# BMS_master_board.net
KiCad netlist of a schematic drawn in EAGLE
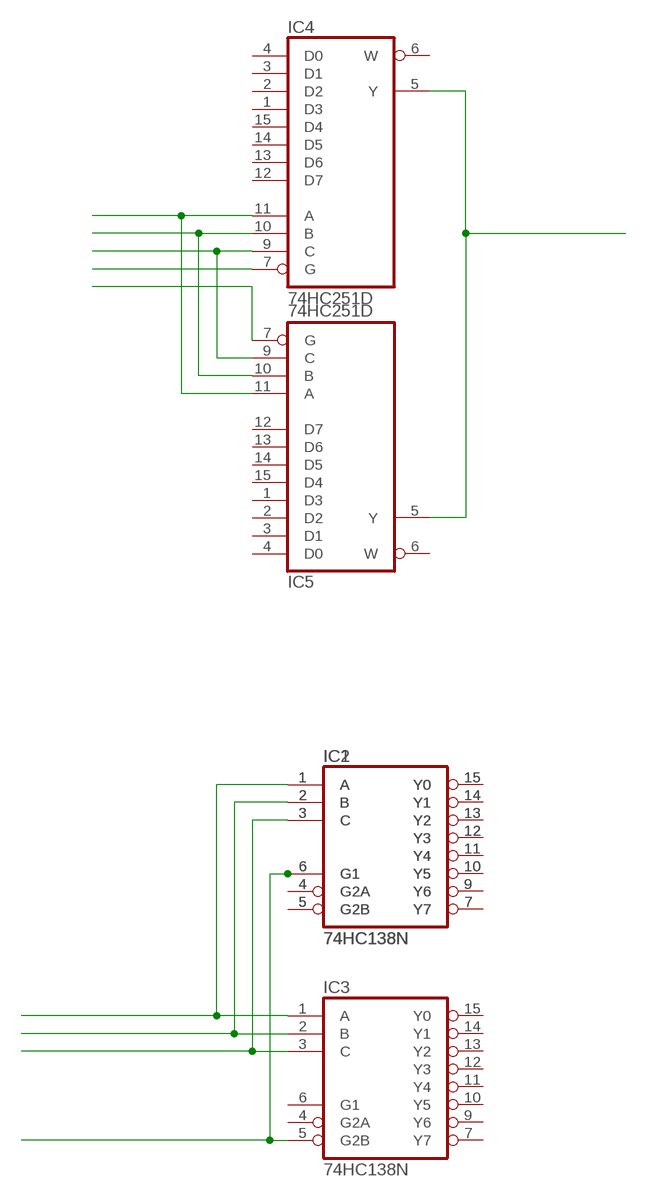
[diagram p0: schematic, sheet 1]

(export (version "E")
  (design (tool "Eeschema 10.0.6"))
  (components
    (comp (ref "IC1")
      (value "74HC138N")
      (footprint "eagle-import:DIL16")
      (libsource (lib "eagle-import") (part "74138NHC"))
    )
    (comp (ref "IC2")
      (value "74HC138N")
      (footprint "eagle-import:DIL16")
      (libsource (lib "eagle-import") (part "74138NHC"))
    )
    (comp (ref "IC3")
      (value "74HC138N")
      (footprint "eagle-import:DIL16")
      (libsource (lib "eagle-import") (part "74138NHC"))
    )
    (comp (ref "IC4")
      (value "74HC251D")
      (footprint "eagle-import:SO16")
      (libsource (lib "eagle-import") (part "74251DHC"))
    )
    (comp (ref "IC5")
      (value "74HC251D")
      (footprint "eagle-import:SO16")
      (libsource (lib "eagle-import") (part "74251DHC"))
    )
  )
  (nets
    (net (code "1") (name "Net-(IC1A-A)") (class "Default")
      (node (ref "IC1") (pin "1") (pinfunction "A_1") (pintype "input"))
      (node (ref "IC2") (pin "1") (pinfunction "A_1") (pintype "input"))
      (node (ref "IC3") (pin "1") (pinfunction "A_1") (pintype "input"))
    )
    (net (code "2") (name "Net-(IC1A-B)") (class "Default")
      (node (ref "IC1") (pin "2") (pinfunction "B_2") (pintype "input"))
      (node (ref "IC2") (pin "2") (pinfunction "B_2") (pintype "input"))
      (node (ref "IC3") (pin "2") (pinfunction "B_2") (pintype "input"))
    )
    (net (code "3") (name "Net-(IC1A-C)") (class "Default")
      (node (ref "IC1") (pin "3") (pinfunction "C_3") (pintype "input"))
      (node (ref "IC2") (pin "3") (pinfunction "C_3") (pintype "input"))
      (node (ref "IC3") (pin "3") (pinfunction "C_3") (pintype "input"))
    )
    (net (code "4") (name "Net-(IC1A-G1)") (class "Default")
      (node (ref "IC1") (pin "6") (pinfunction "G1_6") (pintype "input"))
      (node (ref "IC2") (pin "6") (pinfunction "G1_6") (pintype "input"))
      (node (ref "IC3") (pin "5") (pinfunction "G2B_5") (pintype "input"))
    )
    (net (code "5") (name "Net-(IC1A-G2A)") (class "Default")
      (node (ref "IC1") (pin "4") (pinfunction "G2A_4") (pintype "input"))
      (node (ref "IC2") (pin "4") (pinfunction "G2A_4") (pintype "input"))
    )
    (net (code "6") (name "Net-(IC1A-G2B)") (class "Default")
      (node (ref "IC1") (pin "5") (pinfunction "G2B_5") (pintype "input"))
      (node (ref "IC2") (pin "5") (pinfunction "G2B_5") (pintype "input"))
    )
    (net (code "7") (name "Net-(IC1A-Y0)") (class "Default")
      (node (ref "IC1") (pin "15") (pinfunction "Y0_15") (pintype "output"))
      (node (ref "IC2") (pin "15") (pinfunction "Y0_15") (pintype "output"))
    )
    (net (code "8") (name "Net-(IC1A-Y1)") (class "Default")
      (node (ref "IC1") (pin "14") (pinfunction "Y1_14") (pintype "output"))
      (node (ref "IC2") (pin "14") (pinfunction "Y1_14") (pintype "output"))
    )
    (net (code "9") (name "Net-(IC1A-Y2)") (class "Default")
      (node (ref "IC1") (pin "13") (pinfunction "Y2_13") (pintype "output"))
      (node (ref "IC2") (pin "13") (pinfunction "Y2_13") (pintype "output"))
    )
    (net (code "10") (name "Net-(IC1A-Y3)") (class "Default")
      (node (ref "IC1") (pin "12") (pinfunction "Y3_12") (pintype "output"))
      (node (ref "IC2") (pin "12") (pinfunction "Y3_12") (pintype "output"))
    )
    (net (code "11") (name "Net-(IC1A-Y4)") (class "Default")
      (node (ref "IC1") (pin "11") (pinfunction "Y4_11") (pintype "output"))
      (node (ref "IC2") (pin "11") (pinfunction "Y4_11") (pintype "output"))
    )
    (net (code "12") (name "Net-(IC1A-Y5)") (class "Default")
      (node (ref "IC1") (pin "10") (pinfunction "Y5_10") (pintype "output"))
      (node (ref "IC2") (pin "10") (pinfunction "Y5_10") (pintype "output"))
    )
    (net (code "13") (name "Net-(IC1A-Y6)") (class "Default")
      (node (ref "IC1") (pin "9") (pinfunction "Y6_9") (pintype "output"))
      (node (ref "IC2") (pin "9") (pinfunction "Y6_9") (pintype "output"))
    )
    (net (code "14") (name "Net-(IC1A-Y7)") (class "Default")
      (node (ref "IC1") (pin "7") (pinfunction "Y7_7") (pintype "output"))
      (node (ref "IC2") (pin "7") (pinfunction "Y7_7") (pintype "output"))
    )
    (net (code "15") (name "Net-(IC4A-A)") (class "Default")
      (node (ref "IC4") (pin "11") (pinfunction "A_11") (pintype "input"))
      (node (ref "IC5") (pin "11") (pinfunction "A_11") (pintype "input"))
    )
    (net (code "16") (name "Net-(IC4A-B)") (class "Default")
      (node (ref "IC4") (pin "10") (pinfunction "B_10") (pintype "input"))
      (node (ref "IC5") (pin "10") (pinfunction "B_10") (pintype "input"))
    )
    (net (code "17") (name "Net-(IC4A-C)") (class "Default")
      (node (ref "IC4") (pin "9") (pinfunction "C_9") (pintype "input"))
      (node (ref "IC5") (pin "9") (pinfunction "C_9") (pintype "input"))
    )
    (net (code "18") (name "Net-(IC4A-Y)") (class "Default")
      (node (ref "IC4") (pin "5") (pinfunction "Y_5") (pintype "tri_state"))
      (node (ref "IC5") (pin "5") (pinfunction "Y_5") (pintype "tri_state"))
    )
    (net (code "19") (name "unconnected-(IC3A-G1-Pad6)") (class "Default")
      (node (ref "IC3") (pin "6") (pinfunction "G1_6") (pintype "input"))
    )
    (net (code "20") (name "unconnected-(IC3A-G2A-Pad4)") (class "Default")
      (node (ref "IC3") (pin "4") (pinfunction "G2A_4") (pintype "input"))
    )
    (net (code "21") (name "unconnected-(IC3A-Y0-Pad15)") (class "Default")
      (node (ref "IC3") (pin "15") (pinfunction "Y0_15") (pintype "output"))
    )
    (net (code "22") (name "unconnected-(IC3A-Y1-Pad14)") (class "Default")
      (node (ref "IC3") (pin "14") (pinfunction "Y1_14") (pintype "output"))
    )
    (net (code "23") (name "unconnected-(IC3A-Y2-Pad13)") (class "Default")
      (node (ref "IC3") (pin "13") (pinfunction "Y2_13") (pintype "output"))
    )
    (net (code "24") (name "unconnected-(IC3A-Y3-Pad12)") (class "Default")
      (node (ref "IC3") (pin "12") (pinfunction "Y3_12") (pintype "output"))
    )
    (net (code "25") (name "unconnected-(IC3A-Y4-Pad11)") (class "Default")
      (node (ref "IC3") (pin "11") (pinfunction "Y4_11") (pintype "output"))
    )
    (net (code "26") (name "unconnected-(IC3A-Y5-Pad10)") (class "Default")
      (node (ref "IC3") (pin "10") (pinfunction "Y5_10") (pintype "output"))
    )
    (net (code "27") (name "unconnected-(IC3A-Y6-Pad9)") (class "Default")
      (node (ref "IC3") (pin "9") (pinfunction "Y6_9") (pintype "output"))
    )
    (net (code "28") (name "unconnected-(IC3A-Y7-Pad7)") (class "Default")
      (node (ref "IC3") (pin "7") (pinfunction "Y7_7") (pintype "output"))
    )
    (net (code "29") (name "unconnected-(IC4A-D0-Pad4)") (class "Default")
      (node (ref "IC4") (pin "4") (pinfunction "D0_4") (pintype "input"))
    )
    (net (code "30") (name "unconnected-(IC4A-D1-Pad3)") (class "Default")
      (node (ref "IC4") (pin "3") (pinfunction "D1_3") (pintype "input"))
    )
    (net (code "31") (name "unconnected-(IC4A-D2-Pad2)") (class "Default")
      (node (ref "IC4") (pin "2") (pinfunction "D2_2") (pintype "input"))
    )
    (net (code "32") (name "unconnected-(IC4A-D3-Pad1)") (class "Default")
      (node (ref "IC4") (pin "1") (pinfunction "D3_1") (pintype "input"))
    )
    (net (code "33") (name "unconnected-(IC4A-D4-Pad15)") (class "Default")
      (node (ref "IC4") (pin "15") (pinfunction "D4_15") (pintype "input"))
    )
    (net (code "34") (name "unconnected-(IC4A-D5-Pad14)") (class "Default")
      (node (ref "IC4") (pin "14") (pinfunction "D5_14") (pintype "input"))
    )
    (net (code "35") (name "unconnected-(IC4A-D6-Pad13)") (class "Default")
      (node (ref "IC4") (pin "13") (pinfunction "D6_13") (pintype "input"))
    )
    (net (code "36") (name "unconnected-(IC4A-D7-Pad12)") (class "Default")
      (node (ref "IC4") (pin "12") (pinfunction "D7_12") (pintype "input"))
    )
    (net (code "37") (name "unconnected-(IC4A-G-Pad7)") (class "Default")
      (node (ref "IC4") (pin "7") (pinfunction "G_7") (pintype "input"))
    )
    (net (code "38") (name "unconnected-(IC4A-W-Pad6)") (class "Default")
      (node (ref "IC4") (pin "6") (pinfunction "W_6") (pintype "tri_state"))
    )
    (net (code "39") (name "unconnected-(IC5A-D0-Pad4)") (class "Default")
      (node (ref "IC5") (pin "4") (pinfunction "D0_4") (pintype "input"))
    )
    (net (code "40") (name "unconnected-(IC5A-D1-Pad3)") (class "Default")
      (node (ref "IC5") (pin "3") (pinfunction "D1_3") (pintype "input"))
    )
    (net (code "41") (name "unconnected-(IC5A-D2-Pad2)") (class "Default")
      (node (ref "IC5") (pin "2") (pinfunction "D2_2") (pintype "input"))
    )
    (net (code "42") (name "unconnected-(IC5A-D3-Pad1)") (class "Default")
      (node (ref "IC5") (pin "1") (pinfunction "D3_1") (pintype "input"))
    )
    (net (code "43") (name "unconnected-(IC5A-D4-Pad15)") (class "Default")
      (node (ref "IC5") (pin "15") (pinfunction "D4_15") (pintype "input"))
    )
    (net (code "44") (name "unconnected-(IC5A-D5-Pad14)") (class "Default")
      (node (ref "IC5") (pin "14") (pinfunction "D5_14") (pintype "input"))
    )
    (net (code "45") (name "unconnected-(IC5A-D6-Pad13)") (class "Default")
      (node (ref "IC5") (pin "13") (pinfunction "D6_13") (pintype "input"))
    )
    (net (code "46") (name "unconnected-(IC5A-D7-Pad12)") (class "Default")
      (node (ref "IC5") (pin "12") (pinfunction "D7_12") (pintype "input"))
    )
    (net (code "47") (name "unconnected-(IC5A-G-Pad7)") (class "Default")
      (node (ref "IC5") (pin "7") (pinfunction "G_7") (pintype "input"))
    )
    (net (code "48") (name "unconnected-(IC5A-W-Pad6)") (class "Default")
      (node (ref "IC5") (pin "6") (pinfunction "W_6") (pintype "tri_state"))
    )
  )
)
